# InputBrd.net
KiCad netlist of a schematic drawn in EAGLE
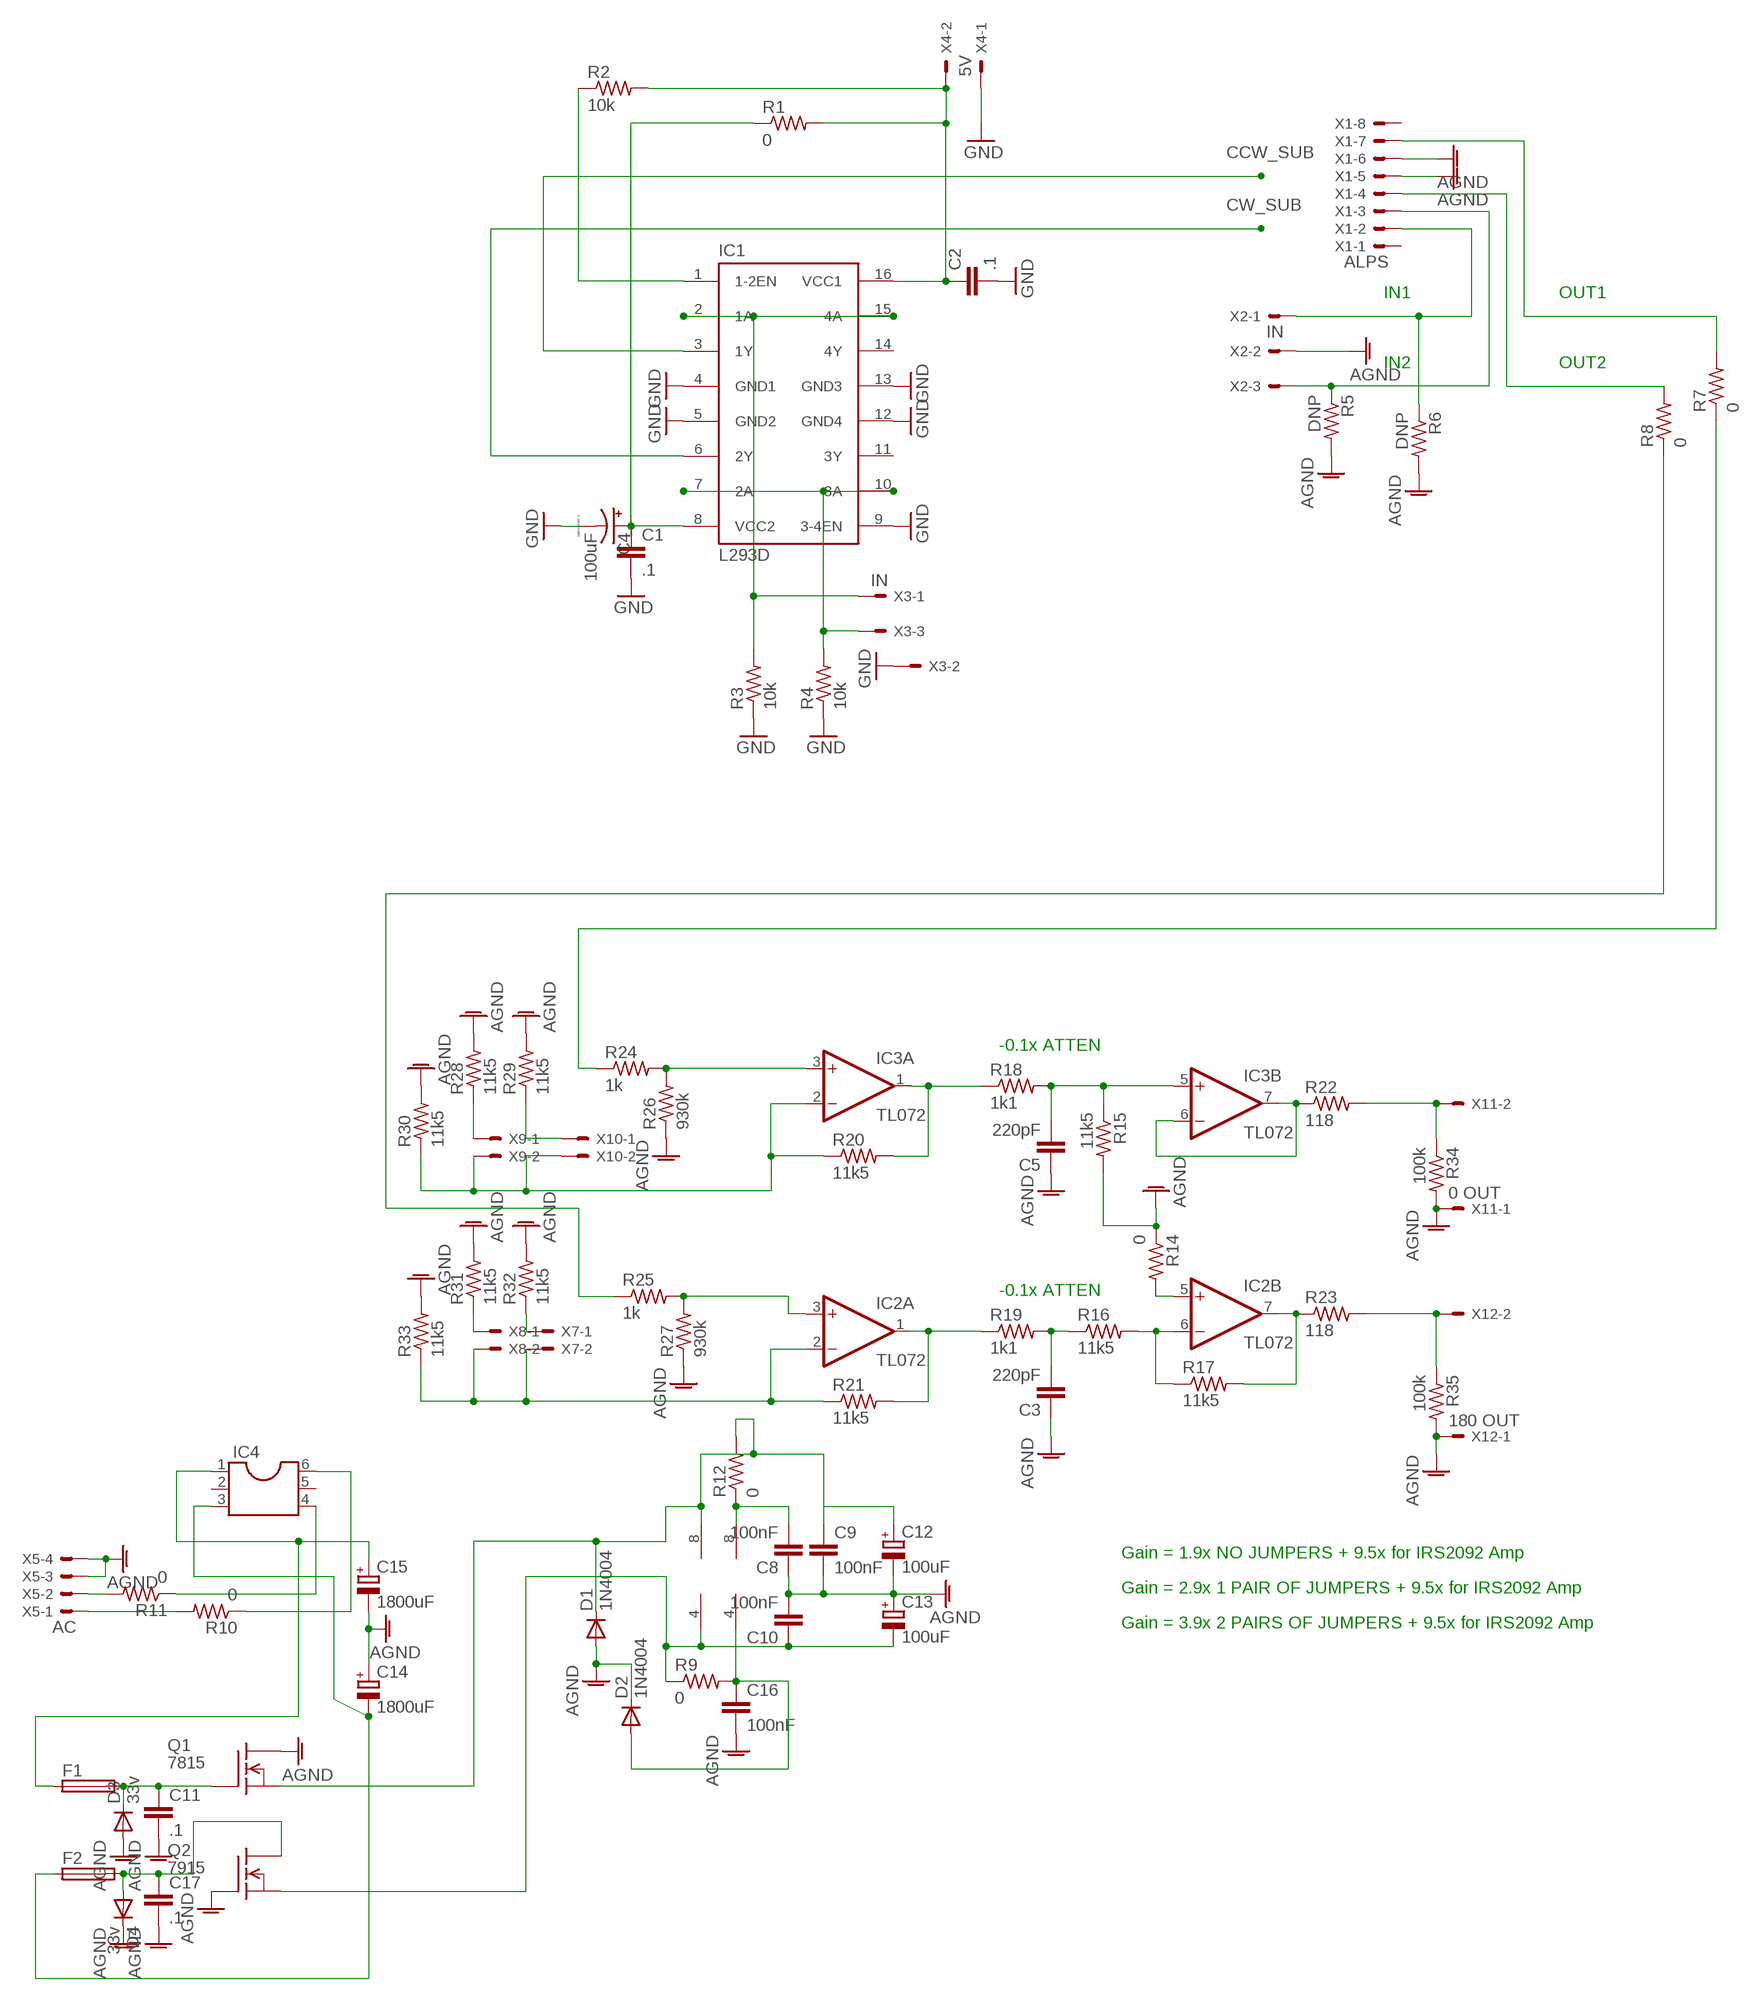
[diagram p0: schematic, sheet 1]

(export (version "E")
  (design (tool "Eeschema 10.0.6"))
  (components
    (comp (ref "C1")
      (value ".1")
      (footprint "eagle-import:C1210")
      (libsource (lib "eagle-import") (part "C-EUC1210"))
    )
    (comp (ref "C2")
      (value ".1")
      (footprint "eagle-import:C1210")
      (libsource (lib "eagle-import") (part "C-EUC1210"))
    )
    (comp (ref "C3")
      (value "220pF")
      (footprint "eagle-import:C050-035X075")
      (libsource (lib "eagle-import") (part "C-EU050-035X075"))
    )
    (comp (ref "C4")
      (value "100uF")
      (footprint "eagle-import:E2,5-6E")
      (libsource (lib "eagle-import") (part "CPOL-USE2,5-6E"))
    )
    (comp (ref "C5")
      (value "220pF")
      (footprint "eagle-import:C050-035X075")
      (libsource (lib "eagle-import") (part "C-EU050-035X075"))
    )
    (comp (ref "C8")
      (value "100nF")
      (footprint "eagle-import:C1210")
      (libsource (lib "eagle-import") (part "C-EUC1210"))
    )
    (comp (ref "C9")
      (value "100nF")
      (footprint "eagle-import:C1210")
      (libsource (lib "eagle-import") (part "C-EUC1210"))
    )
    (comp (ref "C10")
      (value "100nF")
      (footprint "eagle-import:C1210")
      (libsource (lib "eagle-import") (part "C-EUC1210"))
    )
    (comp (ref "C11")
      (value ".1")
      (footprint "eagle-import:C1210")
      (libsource (lib "eagle-import") (part "C-EUC1210"))
    )
    (comp (ref "C12")
      (value "100uF")
      (footprint "eagle-import:E3,5-10")
      (libsource (lib "eagle-import") (part "CPOL-EUE3.5-10"))
    )
    (comp (ref "C13")
      (value "100uF")
      (footprint "eagle-import:E3,5-10")
      (libsource (lib "eagle-import") (part "CPOL-EUE3.5-10"))
    )
    (comp (ref "C14")
      (value "1800uF")
      (footprint "eagle-import:E7,5-16")
      (libsource (lib "eagle-import") (part "CPOL-EUE7.5-16"))
    )
    (comp (ref "C15")
      (value "1800uF")
      (footprint "eagle-import:E7,5-16")
      (libsource (lib "eagle-import") (part "CPOL-EUE7.5-16"))
    )
    (comp (ref "C16")
      (value "100nF")
      (footprint "eagle-import:C1210")
      (libsource (lib "eagle-import") (part "C-EUC1210"))
    )
    (comp (ref "C17")
      (value ".1")
      (footprint "eagle-import:C1210")
      (libsource (lib "eagle-import") (part "C-EUC1210"))
    )
    (comp (ref "D1")
      (value "1N4004")
      (footprint "eagle-import:DO41-10")
      (libsource (lib "eagle-import") (part "1N4004"))
    )
    (comp (ref "D2")
      (value "1N4004")
      (footprint "eagle-import:DO41-10")
      (libsource (lib "eagle-import") (part "1N4004"))
    )
    (comp (ref "D3")
      (value "33v")
      (footprint "eagle-import:TO220ACS")
      (libsource (lib "eagle-import") (part "BYT08P"))
    )
    (comp (ref "D4")
      (value "33v")
      (footprint "eagle-import:TO220ACS")
      (libsource (lib "eagle-import") (part "BYT08P"))
    )
    (comp (ref "F1")
      (value "19560")
      (footprint "eagle-import:19560")
      (fields (field (name "MPN") "56000001009"))
      (libsource (lib "eagle-import") (part "19560"))
    )
    (comp (ref "F2")
      (value "19560")
      (footprint "eagle-import:19560")
      (fields (field (name "MPN") "56000001009"))
      (libsource (lib "eagle-import") (part "19560"))
    )
    (comp (ref "IC1")
      (value "L293D")
      (footprint "eagle-import:DIL16")
      (libsource (lib "eagle-import") (part "L293D"))
    )
    (comp (ref "IC2")
      (value "TL072")
      (footprint "eagle-import:DIL08")
      (libsource (lib "eagle-import") (part "1458NLM"))
    )
    (comp (ref "IC3")
      (value "TL072")
      (footprint "eagle-import:DIL08")
      (libsource (lib "eagle-import") (part "1458NLM"))
    )
    (comp (ref "IC4")
      (value "DIL6")
      (footprint "eagle-import:DIL06")
      (libsource (lib "eagle-import") (part "DIL6"))
    )
    (comp (ref "Q1")
      (value "7815")
      (footprint "eagle-import:TO220")
      (libsource (lib "eagle-import") (part "BUZ71"))
    )
    (comp (ref "Q2")
      (value "7915")
      (footprint "eagle-import:TO220")
      (libsource (lib "eagle-import") (part "BUZ71"))
    )
    (comp (ref "R1")
      (value "0")
      (footprint "eagle-import:0207_15")
      (libsource (lib "eagle-import") (part "R-US_0207/15"))
    )
    (comp (ref "R2")
      (value "10k")
      (footprint "eagle-import:R1210")
      (libsource (lib "eagle-import") (part "R-US_R1210"))
    )
    (comp (ref "R3")
      (value "10k")
      (footprint "eagle-import:R1210")
      (libsource (lib "eagle-import") (part "R-US_R1210"))
    )
    (comp (ref "R4")
      (value "10k")
      (footprint "eagle-import:R1210")
      (libsource (lib "eagle-import") (part "R-US_R1210"))
    )
    (comp (ref "R5")
      (value "DNP")
      (footprint "eagle-import:0309_10")
      (libsource (lib "eagle-import") (part "R-US_0309/10"))
    )
    (comp (ref "R6")
      (value "DNP")
      (footprint "eagle-import:0309_10")
      (libsource (lib "eagle-import") (part "R-US_0309/10"))
    )
    (comp (ref "R7")
      (value "0")
      (footprint "eagle-import:0309_12")
      (libsource (lib "eagle-import") (part "R-US_0309/12"))
    )
    (comp (ref "R8")
      (value "0")
      (footprint "eagle-import:0309_12")
      (libsource (lib "eagle-import") (part "R-US_0309/12"))
    )
    (comp (ref "R9")
      (value "0")
      (footprint "eagle-import:0309_10")
      (libsource (lib "eagle-import") (part "R-US_0309/10"))
    )
    (comp (ref "R10")
      (value "0")
      (footprint "eagle-import:0309V")
      (libsource (lib "eagle-import") (part "R-US_0309/V"))
    )
    (comp (ref "R11")
      (value "0")
      (footprint "eagle-import:0309V")
      (libsource (lib "eagle-import") (part "R-US_0309/V"))
    )
    (comp (ref "R12")
      (value "0")
      (footprint "eagle-import:0309_10")
      (libsource (lib "eagle-import") (part "R-US_0309/10"))
    )
    (comp (ref "R14")
      (value "0")
      (footprint "eagle-import:0309_12")
      (libsource (lib "eagle-import") (part "R-US_0309/12"))
    )
    (comp (ref "R15")
      (value "11k5")
      (footprint "eagle-import:0309_12")
      (libsource (lib "eagle-import") (part "R-US_0309/12"))
    )
    (comp (ref "R16")
      (value "11k5")
      (footprint "eagle-import:0309_10")
      (libsource (lib "eagle-import") (part "R-US_0309/10"))
    )
    (comp (ref "R17")
      (value "11k5")
      (footprint "eagle-import:0309_10")
      (libsource (lib "eagle-import") (part "R-US_0309/10"))
    )
    (comp (ref "R18")
      (value "1k1")
      (footprint "eagle-import:0309_12")
      (libsource (lib "eagle-import") (part "R-US_0309/12"))
    )
    (comp (ref "R19")
      (value "1k1")
      (footprint "eagle-import:0309_12")
      (libsource (lib "eagle-import") (part "R-US_0309/12"))
    )
    (comp (ref "R20")
      (value "11k5")
      (footprint "eagle-import:0309_10")
      (libsource (lib "eagle-import") (part "R-US_0309/10"))
    )
    (comp (ref "R21")
      (value "11k5")
      (footprint "eagle-import:0309_10")
      (libsource (lib "eagle-import") (part "R-US_0309/10"))
    )
    (comp (ref "R22")
      (value "118")
      (footprint "eagle-import:0309_12")
      (libsource (lib "eagle-import") (part "R-US_0309/12"))
    )
    (comp (ref "R23")
      (value "118")
      (footprint "eagle-import:0309_10")
      (libsource (lib "eagle-import") (part "R-US_0309/10"))
    )
    (comp (ref "R24")
      (value "1k")
      (footprint "eagle-import:0411_15")
      (libsource (lib "eagle-import") (part "R-US_0411/15"))
    )
    (comp (ref "R25")
      (value "1k")
      (footprint "eagle-import:0309_12")
      (libsource (lib "eagle-import") (part "R-US_0309/12"))
    )
    (comp (ref "R26")
      (value "930k")
      (footprint "eagle-import:0309_10")
      (libsource (lib "eagle-import") (part "R-US_0309/10"))
    )
    (comp (ref "R27")
      (value "930k")
      (footprint "eagle-import:0309_10")
      (libsource (lib "eagle-import") (part "R-US_0309/10"))
    )
    (comp (ref "R28")
      (value "11k5")
      (footprint "eagle-import:0309_10")
      (libsource (lib "eagle-import") (part "R-US_0309/10"))
    )
    (comp (ref "R29")
      (value "11k5")
      (footprint "eagle-import:0309_10")
      (libsource (lib "eagle-import") (part "R-US_0309/10"))
    )
    (comp (ref "R30")
      (value "11k5")
      (footprint "eagle-import:0309_10")
      (libsource (lib "eagle-import") (part "R-US_0309/10"))
    )
    (comp (ref "R31")
      (value "11k5")
      (footprint "eagle-import:0309_10")
      (libsource (lib "eagle-import") (part "R-US_0309/10"))
    )
    (comp (ref "R32")
      (value "11k5")
      (footprint "eagle-import:0309_10")
      (libsource (lib "eagle-import") (part "R-US_0309/10"))
    )
    (comp (ref "R33")
      (value "11k5")
      (footprint "eagle-import:0309_10")
      (libsource (lib "eagle-import") (part "R-US_0309/10"))
    )
    (comp (ref "R34")
      (value "100k")
      (footprint "eagle-import:0309_12")
      (libsource (lib "eagle-import") (part "R-US_0309/12"))
    )
    (comp (ref "R35")
      (value "100k")
      (footprint "eagle-import:0309_10")
      (libsource (lib "eagle-import") (part "R-US_0309/10"))
    )
    (comp (ref "X1")
      (value "ALPS")
      (footprint "eagle-import:22-23-2081")
      (fields (field (name "MF") "MOLEX") (field (name "MPN") "22-23-2081"))
      (libsource (lib "eagle-import") (part "22-23-2081"))
    )
    (comp (ref "X2")
      (value "IN")
      (footprint "eagle-import:22-23-2031")
      (fields (field (name "MF") "MOLEX") (field (name "MPN") "22-23-2031"))
      (libsource (lib "eagle-import") (part "22-23-2031"))
    )
    (comp (ref "X3")
      (value "IN")
      (footprint "eagle-import:22-23-2031")
      (fields (field (name "MF") "MOLEX") (field (name "MPN") "22-23-2031"))
      (libsource (lib "eagle-import") (part "22-23-2031"))
    )
    (comp (ref "X4")
      (value "5V")
      (footprint "eagle-import:22-23-2021")
      (fields (field (name "MF") "MOLEX") (field (name "MPN") "22-23-2021"))
      (libsource (lib "eagle-import") (part "22-23-2021"))
    )
    (comp (ref "X5")
      (value "AC")
      (footprint "eagle-import:5566-4")
      (libsource (lib "eagle-import") (part "5566-4"))
    )
    (comp (ref "X7")
      (value "22-23-2021")
      (footprint "eagle-import:22-23-2021")
      (fields (field (name "MF") "MOLEX"))
      (libsource (lib "eagle-import") (part "22-23-2021"))
    )
    (comp (ref "X8")
      (value "22-23-2021")
      (footprint "eagle-import:22-23-2021")
      (fields (field (name "MF") "MOLEX"))
      (libsource (lib "eagle-import") (part "22-23-2021"))
    )
    (comp (ref "X9")
      (value "22-23-2021")
      (footprint "eagle-import:22-23-2021")
      (fields (field (name "MF") "MOLEX"))
      (libsource (lib "eagle-import") (part "22-23-2021"))
    )
    (comp (ref "X10")
      (value "22-23-2021")
      (footprint "eagle-import:22-23-2021")
      (fields (field (name "MF") "MOLEX"))
      (libsource (lib "eagle-import") (part "22-23-2021"))
    )
    (comp (ref "X11")
      (value "0 OUT")
      (footprint "eagle-import:22-23-2021")
      (fields (field (name "MF") "MOLEX") (field (name "MPN") "22-23-2021"))
      (libsource (lib "eagle-import") (part "22-23-2021"))
    )
    (comp (ref "X12")
      (value "180 OUT")
      (footprint "eagle-import:22-23-2021")
      (fields (field (name "MF") "MOLEX") (field (name "MPN") "22-23-2021"))
      (libsource (lib "eagle-import") (part "22-23-2021"))
    )
  )
  (nets
    (net (code "1") (name "/CCW_SUB") (class "Default")
      (node (ref "IC1") (pin "3") (pinfunction "1Y_3") (pintype "output"))
    )
    (net (code "2") (name "/CW_SUB") (class "Default")
      (node (ref "IC1") (pin "6") (pinfunction "2Y_6") (pintype "output"))
    )
    (net (code "3") (name "AGND") (class "Default")
      (node (ref "C10") (pin "2") (pinfunction "2_2") (pintype "passive"))
      (node (ref "C11") (pin "2") (pinfunction "2_2") (pintype "passive"))
      (node (ref "C12") (pin "-") (pinfunction "-_-") (pintype "passive"))
      (node (ref "C13") (pin "+") (pinfunction "+_+") (pintype "passive"))
      (node (ref "C14") (pin "+") (pinfunction "+_+") (pintype "passive"))
      (node (ref "C15") (pin "-") (pinfunction "-_-") (pintype "passive"))
      (node (ref "C16") (pin "2") (pinfunction "2_2") (pintype "passive"))
      (node (ref "C17") (pin "2") (pinfunction "2_2") (pintype "passive"))
      (node (ref "C3") (pin "1") (pinfunction "1_1") (pintype "passive"))
      (node (ref "C5") (pin "1") (pinfunction "1_1") (pintype "passive"))
      (node (ref "C8") (pin "1") (pinfunction "1_1") (pintype "passive"))
      (node (ref "C9") (pin "2") (pinfunction "2_2") (pintype "passive"))
      (node (ref "D1") (pin "A") (pinfunction "A_A") (pintype "passive"))
      (node (ref "D2") (pin "C") (pinfunction "C_C") (pintype "passive"))
      (node (ref "D3") (pin "A") (pinfunction "A_A") (pintype "passive"))
      (node (ref "D4") (pin "C") (pinfunction "C_C") (pintype "passive"))
      (node (ref "Q1") (pin "2") (pinfunction "D_2") (pintype "passive"))
      (node (ref "Q2") (pin "1") (pinfunction "G_1") (pintype "passive"))
      (node (ref "R14") (pin "1") (pinfunction "1_1") (pintype "passive"))
      (node (ref "R15") (pin "2") (pinfunction "2_2") (pintype "passive"))
      (node (ref "R26") (pin "1") (pinfunction "1_1") (pintype "passive"))
      (node (ref "R27") (pin "1") (pinfunction "1_1") (pintype "passive"))
      (node (ref "R28") (pin "2") (pinfunction "2_2") (pintype "passive"))
      (node (ref "R29") (pin "2") (pinfunction "2_2") (pintype "passive"))
      (node (ref "R30") (pin "2") (pinfunction "2_2") (pintype "passive"))
      (node (ref "R31") (pin "2") (pinfunction "2_2") (pintype "passive"))
      (node (ref "R32") (pin "2") (pinfunction "2_2") (pintype "passive"))
      (node (ref "R33") (pin "2") (pinfunction "2_2") (pintype "passive"))
      (node (ref "R34") (pin "2") (pinfunction "2_2") (pintype "passive"))
      (node (ref "R35") (pin "2") (pinfunction "2_2") (pintype "passive"))
      (node (ref "R5") (pin "2") (pinfunction "2_2") (pintype "passive"))
      (node (ref "R6") (pin "2") (pinfunction "2_2") (pintype "passive"))
      (node (ref "X1") (pin "5") (pinfunction "S_5") (pintype "passive"))
      (node (ref "X1") (pin "6") (pinfunction "S_6") (pintype "passive"))
      (node (ref "X11") (pin "1") (pinfunction "S_1") (pintype "passive"))
      (node (ref "X12") (pin "1") (pinfunction "S_1") (pintype "passive"))
      (node (ref "X2") (pin "2") (pinfunction "S_2") (pintype "passive"))
      (node (ref "X5") (pin "3") (pinfunction "S_3") (pintype "passive"))
      (node (ref "X5") (pin "4") (pinfunction "S_4") (pintype "passive"))
    )
    (net (code "4") (name "GND") (class "Default")
      (node (ref "C1") (pin "2") (pinfunction "2_2") (pintype "passive"))
      (node (ref "C2") (pin "2") (pinfunction "2_2") (pintype "passive"))
      (node (ref "C4") (pin "-") (pinfunction "-_-") (pintype "passive"))
      (node (ref "IC1") (pin "12") (pinfunction "GND4_12") (pintype "power_in"))
      (node (ref "IC1") (pin "13") (pinfunction "GND3_13") (pintype "power_in"))
      (node (ref "IC1") (pin "4") (pinfunction "GND1_4") (pintype "power_in"))
      (node (ref "IC1") (pin "5") (pinfunction "GND2_5") (pintype "power_in"))
      (node (ref "IC1") (pin "9") (pinfunction "3-4EN_9") (pintype "input"))
      (node (ref "R3") (pin "1") (pinfunction "1_1") (pintype "passive"))
      (node (ref "R4") (pin "1") (pinfunction "1_1") (pintype "passive"))
      (node (ref "X3") (pin "2") (pinfunction "S_2") (pintype "passive"))
      (node (ref "X4") (pin "1") (pinfunction "S_1") (pintype "passive"))
    )
    (net (code "5") (name "Net-(C3-Pad2)") (class "Default")
      (node (ref "C3") (pin "2") (pinfunction "2_2") (pintype "passive"))
      (node (ref "R16") (pin "1") (pinfunction "1_1") (pintype "passive"))
      (node (ref "R19") (pin "2") (pinfunction "2_2") (pintype "passive"))
    )
    (net (code "6") (name "Net-(C14-Pad-)") (class "Default")
      (node (ref "C14") (pin "-") (pinfunction "-_-") (pintype "passive"))
      (node (ref "F2") (pin "1") (pinfunction "1_1") (pintype "passive"))
      (node (ref "IC4") (pin "3") (pinfunction "3_3") (pintype "passive"))
    )
    (net (code "7") (name "Net-(C15-Pad+)") (class "Default")
      (node (ref "C15") (pin "+") (pinfunction "+_+") (pintype "passive"))
      (node (ref "F1") (pin "1") (pinfunction "1_1") (pintype "passive"))
      (node (ref "IC4") (pin "1") (pinfunction "1_1") (pintype "passive"))
    )
    (net (code "8") (name "Net-(IC1-1-2EN)") (class "Default")
      (node (ref "IC1") (pin "1") (pinfunction "1-2EN_1") (pintype "input"))
      (node (ref "R2") (pin "1") (pinfunction "1_1") (pintype "passive"))
    )
    (net (code "9") (name "Net-(IC1-1A)") (class "Default")
      (node (ref "IC1") (pin "15") (pinfunction "4A_15") (pintype "input"))
      (node (ref "IC1") (pin "2") (pinfunction "1A_2") (pintype "input"))
      (node (ref "R3") (pin "2") (pinfunction "2_2") (pintype "passive"))
      (node (ref "X3") (pin "1") (pinfunction "S_1") (pintype "passive"))
    )
    (net (code "10") (name "Net-(IC1-2A)") (class "Default")
      (node (ref "IC1") (pin "10") (pinfunction "3A_10") (pintype "input"))
      (node (ref "IC1") (pin "7") (pinfunction "2A_7") (pintype "input"))
      (node (ref "R4") (pin "2") (pinfunction "2_2") (pintype "passive"))
      (node (ref "X3") (pin "3") (pinfunction "S_3") (pintype "passive"))
    )
    (net (code "11") (name "Net-(IC1-VCC1)") (class "Default")
      (node (ref "C2") (pin "1") (pinfunction "1_1") (pintype "passive"))
      (node (ref "IC1") (pin "16") (pinfunction "VCC1_16") (pintype "power_in"))
      (node (ref "R1") (pin "2") (pinfunction "2_2") (pintype "passive"))
      (node (ref "R2") (pin "2") (pinfunction "2_2") (pintype "passive"))
      (node (ref "X4") (pin "2") (pinfunction "S_2") (pintype "passive"))
    )
    (net (code "12") (name "Net-(IC1-VCC2)") (class "Default")
      (node (ref "C1") (pin "1") (pinfunction "1_1") (pintype "passive"))
      (node (ref "C4") (pin "+") (pinfunction "+_+") (pintype "passive"))
      (node (ref "IC1") (pin "8") (pinfunction "VCC2_8") (pintype "power_in"))
      (node (ref "R1") (pin "1") (pinfunction "1_1") (pintype "passive"))
    )
    (net (code "13") (name "Net-(IC2A-+IN)") (class "Default")
      (node (ref "IC2") (pin "3") (pinfunction "+IN_3") (pintype "input"))
      (node (ref "R25") (pin "2") (pinfunction "2_2") (pintype "passive"))
      (node (ref "R27") (pin "2") (pinfunction "2_2") (pintype "passive"))
    )
    (net (code "14") (name "Net-(IC2A--IN)") (class "Default")
      (node (ref "IC2") (pin "2") (pinfunction "-IN_2") (pintype "input"))
      (node (ref "R21") (pin "1") (pinfunction "1_1") (pintype "passive"))
      (node (ref "R33") (pin "1") (pinfunction "1_1") (pintype "passive"))
      (node (ref "X7") (pin "2") (pinfunction "S_2") (pintype "passive"))
      (node (ref "X8") (pin "2") (pinfunction "S_2") (pintype "passive"))
    )
    (net (code "15") (name "Net-(IC2A-OUT)") (class "Default")
      (node (ref "IC2") (pin "1") (pinfunction "OUT_1") (pintype "output"))
      (node (ref "R19") (pin "1") (pinfunction "1_1") (pintype "passive"))
      (node (ref "R21") (pin "2") (pinfunction "2_2") (pintype "passive"))
    )
    (net (code "16") (name "Net-(IC2B-+IN)") (class "Default")
      (node (ref "IC2") (pin "5") (pinfunction "+IN_5") (pintype "input"))
      (node (ref "R14") (pin "2") (pinfunction "2_2") (pintype "passive"))
    )
    (net (code "17") (name "Net-(IC2B--IN)") (class "Default")
      (node (ref "IC2") (pin "6") (pinfunction "-IN_6") (pintype "input"))
      (node (ref "R16") (pin "2") (pinfunction "2_2") (pintype "passive"))
      (node (ref "R17") (pin "1") (pinfunction "1_1") (pintype "passive"))
    )
    (net (code "18") (name "Net-(IC2B-OUT)") (class "Default")
      (node (ref "IC2") (pin "7") (pinfunction "OUT_7") (pintype "output"))
      (node (ref "R17") (pin "2") (pinfunction "2_2") (pintype "passive"))
      (node (ref "R23") (pin "1") (pinfunction "1_1") (pintype "passive"))
    )
    (net (code "19") (name "Net-(IC2C-V+)") (class "Default")
      (node (ref "C12") (pin "+") (pinfunction "+_+") (pintype "passive"))
      (node (ref "C9") (pin "1") (pinfunction "1_1") (pintype "passive"))
      (node (ref "D1") (pin "C") (pinfunction "C_C") (pintype "passive"))
      (node (ref "IC2") (pin "8") (pinfunction "V+_8") (pintype "power_in"))
      (node (ref "Q1") (pin "3") (pinfunction "S_3") (pintype "passive"))
      (node (ref "R12") (pin "2") (pinfunction "2_2") (pintype "passive"))
    )
    (net (code "20") (name "Net-(IC2C-V-)") (class "Default")
      (node (ref "C10") (pin "1") (pinfunction "1_1") (pintype "passive"))
      (node (ref "C13") (pin "-") (pinfunction "-_-") (pintype "passive"))
      (node (ref "IC2") (pin "4") (pinfunction "V-_4") (pintype "power_in"))
      (node (ref "Q2") (pin "3") (pinfunction "S_3") (pintype "passive"))
      (node (ref "R9") (pin "1") (pinfunction "1_1") (pintype "passive"))
    )
    (net (code "21") (name "Net-(IC3A-+IN)") (class "Default")
      (node (ref "IC3") (pin "3") (pinfunction "+IN_3") (pintype "input"))
      (node (ref "R24") (pin "2") (pinfunction "2_2") (pintype "passive"))
      (node (ref "R26") (pin "2") (pinfunction "2_2") (pintype "passive"))
    )
    (net (code "22") (name "Net-(IC3A--IN)") (class "Default")
      (node (ref "IC3") (pin "2") (pinfunction "-IN_2") (pintype "input"))
      (node (ref "R20") (pin "1") (pinfunction "1_1") (pintype "passive"))
      (node (ref "R30") (pin "1") (pinfunction "1_1") (pintype "passive"))
      (node (ref "X10") (pin "2") (pinfunction "S_2") (pintype "passive"))
      (node (ref "X9") (pin "2") (pinfunction "S_2") (pintype "passive"))
    )
    (net (code "23") (name "Net-(IC3A-OUT)") (class "Default")
      (node (ref "IC3") (pin "1") (pinfunction "OUT_1") (pintype "output"))
      (node (ref "R18") (pin "1") (pinfunction "1_1") (pintype "passive"))
      (node (ref "R20") (pin "2") (pinfunction "2_2") (pintype "passive"))
    )
    (net (code "24") (name "Net-(IC3B-+IN)") (class "Default")
      (node (ref "C5") (pin "2") (pinfunction "2_2") (pintype "passive"))
      (node (ref "IC3") (pin "5") (pinfunction "+IN_5") (pintype "input"))
      (node (ref "R15") (pin "1") (pinfunction "1_1") (pintype "passive"))
      (node (ref "R18") (pin "2") (pinfunction "2_2") (pintype "passive"))
    )
    (net (code "25") (name "Net-(IC3B--IN)") (class "Default")
      (node (ref "IC3") (pin "6") (pinfunction "-IN_6") (pintype "input"))
      (node (ref "IC3") (pin "7") (pinfunction "OUT_7") (pintype "output"))
      (node (ref "R22") (pin "1") (pinfunction "1_1") (pintype "passive"))
    )
    (net (code "26") (name "Net-(IC3C-V+)") (class "Default")
      (node (ref "C8") (pin "2") (pinfunction "2_2") (pintype "passive"))
      (node (ref "IC3") (pin "8") (pinfunction "V+_8") (pintype "power_in"))
      (node (ref "R12") (pin "1") (pinfunction "1_1") (pintype "passive"))
    )
    (net (code "27") (name "Net-(IC3C-V-)") (class "Default")
      (node (ref "C16") (pin "1") (pinfunction "1_1") (pintype "passive"))
      (node (ref "D2") (pin "A") (pinfunction "A_A") (pintype "passive"))
      (node (ref "IC3") (pin "4") (pinfunction "V-_4") (pintype "power_in"))
      (node (ref "R9") (pin "2") (pinfunction "2_2") (pintype "passive"))
    )
    (net (code "28") (name "Net-(IC4-Pad4)") (class "Default")
      (node (ref "IC4") (pin "4") (pinfunction "4_4") (pintype "passive"))
      (node (ref "R11") (pin "1") (pinfunction "1_1") (pintype "passive"))
    )
    (net (code "29") (name "Net-(IC4-Pad6)") (class "Default")
      (node (ref "IC4") (pin "6") (pinfunction "6_6") (pintype "passive"))
      (node (ref "R10") (pin "1") (pinfunction "1_1") (pintype "passive"))
    )
    (net (code "30") (name "Net-(Q1-G)") (class "Default")
      (node (ref "C11") (pin "1") (pinfunction "1_1") (pintype "passive"))
      (node (ref "D3") (pin "C") (pinfunction "C_C") (pintype "passive"))
      (node (ref "F1") (pin "2") (pinfunction "2_2") (pintype "passive"))
      (node (ref "Q1") (pin "1") (pinfunction "G_1") (pintype "passive"))
    )
    (net (code "31") (name "Net-(Q2-D)") (class "Default")
      (node (ref "C17") (pin "1") (pinfunction "1_1") (pintype "passive"))
      (node (ref "D4") (pin "A") (pinfunction "A_A") (pintype "passive"))
      (node (ref "F2") (pin "2") (pinfunction "2_2") (pintype "passive"))
      (node (ref "Q2") (pin "2") (pinfunction "D_2") (pintype "passive"))
    )
    (net (code "32") (name "Net-(R24-Pad1)") (class "Default")
      (node (ref "R24") (pin "1") (pinfunction "1_1") (pintype "passive"))
      (node (ref "R7") (pin "1") (pinfunction "1_1") (pintype "passive"))
    )
    (net (code "33") (name "Net-(R25-Pad1)") (class "Default")
      (node (ref "R25") (pin "1") (pinfunction "1_1") (pintype "passive"))
      (node (ref "R8") (pin "1") (pinfunction "1_1") (pintype "passive"))
    )
    (net (code "34") (name "Net-(X1B-S)") (class "Default")
      (node (ref "R6") (pin "1") (pinfunction "1_1") (pintype "passive"))
      (node (ref "X1") (pin "2") (pinfunction "S_2") (pintype "passive"))
      (node (ref "X2") (pin "1") (pinfunction "S_1") (pintype "passive"))
    )
    (net (code "35") (name "Net-(X1C-S)") (class "Default")
      (node (ref "R5") (pin "1") (pinfunction "1_1") (pintype "passive"))
      (node (ref "X1") (pin "3") (pinfunction "S_3") (pintype "passive"))
      (node (ref "X2") (pin "3") (pinfunction "S_3") (pintype "passive"))
    )
    (net (code "36") (name "Net-(X1D-S)") (class "Default")
      (node (ref "R8") (pin "2") (pinfunction "2_2") (pintype "passive"))
      (node (ref "X1") (pin "4") (pinfunction "S_4") (pintype "passive"))
    )
    (net (code "37") (name "Net-(X1G-S)") (class "Default")
      (node (ref "R7") (pin "2") (pinfunction "2_2") (pintype "passive"))
      (node (ref "X1") (pin "7") (pinfunction "S_7") (pintype "passive"))
    )
    (net (code "38") (name "Net-(X5A-S)") (class "Default")
      (node (ref "R10") (pin "2") (pinfunction "2_2") (pintype "passive"))
      (node (ref "X5") (pin "1") (pinfunction "S_1") (pintype "passive"))
    )
    (net (code "39") (name "Net-(X5B-S)") (class "Default")
      (node (ref "R11") (pin "2") (pinfunction "2_2") (pintype "passive"))
      (node (ref "X5") (pin "2") (pinfunction "S_2") (pintype "passive"))
    )
    (net (code "40") (name "Net-(X7A-S)") (class "Default")
      (node (ref "R32") (pin "1") (pinfunction "1_1") (pintype "passive"))
      (node (ref "X7") (pin "1") (pinfunction "S_1") (pintype "passive"))
    )
    (net (code "41") (name "Net-(X8A-S)") (class "Default")
      (node (ref "R31") (pin "1") (pinfunction "1_1") (pintype "passive"))
      (node (ref "X8") (pin "1") (pinfunction "S_1") (pintype "passive"))
    )
    (net (code "42") (name "Net-(X9A-S)") (class "Default")
      (node (ref "R28") (pin "1") (pinfunction "1_1") (pintype "passive"))
      (node (ref "X9") (pin "1") (pinfunction "S_1") (pintype "passive"))
    )
    (net (code "43") (name "Net-(X10A-S)") (class "Default")
      (node (ref "R29") (pin "1") (pinfunction "1_1") (pintype "passive"))
      (node (ref "X10") (pin "1") (pinfunction "S_1") (pintype "passive"))
    )
    (net (code "44") (name "Net-(X11B-S)") (class "Default")
      (node (ref "R22") (pin "2") (pinfunction "2_2") (pintype "passive"))
      (node (ref "R34") (pin "1") (pinfunction "1_1") (pintype "passive"))
      (node (ref "X11") (pin "2") (pinfunction "S_2") (pintype "passive"))
    )
    (net (code "45") (name "Net-(X12B-S)") (class "Default")
      (node (ref "R23") (pin "2") (pinfunction "2_2") (pintype "passive"))
      (node (ref "R35") (pin "1") (pinfunction "1_1") (pintype "passive"))
      (node (ref "X12") (pin "2") (pinfunction "S_2") (pintype "passive"))
    )
    (net (code "46") (name "unconnected-(IC1-3Y-Pad11)") (class "Default")
      (node (ref "IC1") (pin "11") (pinfunction "3Y_11") (pintype "output"))
    )
    (net (code "47") (name "unconnected-(IC1-4Y-Pad14)") (class "Default")
      (node (ref "IC1") (pin "14") (pinfunction "4Y_14") (pintype "output"))
    )
    (net (code "48") (name "unconnected-(IC4-Pad2)") (class "Default")
      (node (ref "IC4") (pin "2") (pinfunction "2_2") (pintype "passive"))
    )
    (net (code "49") (name "unconnected-(IC4-Pad5)") (class "Default")
      (node (ref "IC4") (pin "5") (pinfunction "5_5") (pintype "passive"))
    )
    (net (code "50") (name "unconnected-(X1A-S-Pad1)") (class "Default")
      (node (ref "X1") (pin "1") (pinfunction "S_1") (pintype "passive"))
    )
    (net (code "51") (name "unconnected-(X1H-S-Pad8)") (class "Default")
      (node (ref "X1") (pin "8") (pinfunction "S_8") (pintype "passive"))
    )
  )
)
